# dcc_sniffer_nano.net
KiCad netlist of a schematic drawn in EAGLE
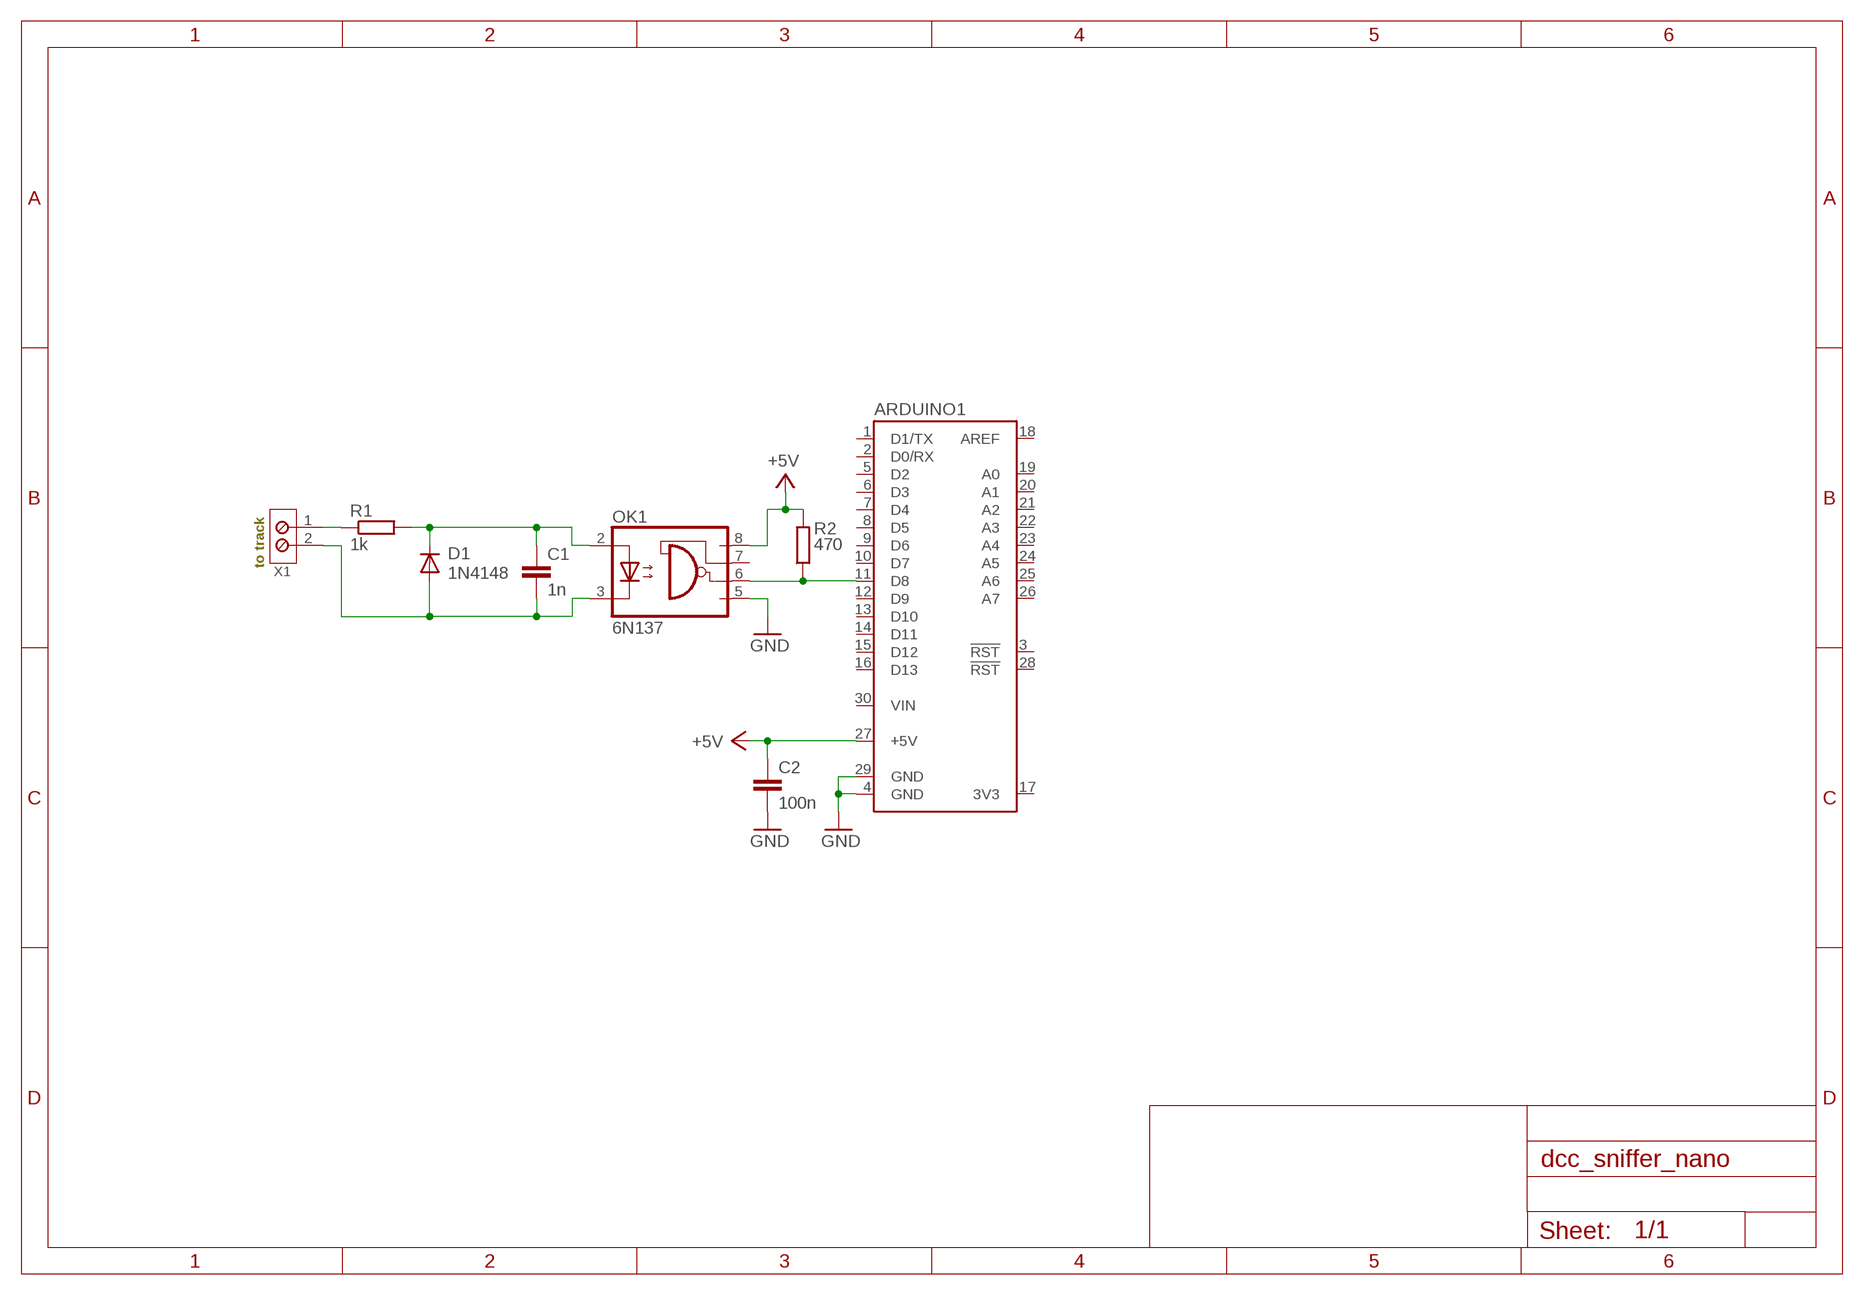
[diagram p0: schematic, sheet 1]

(export (version "E")
  (design (tool "Eeschema 10.0.6"))
  (components
    (comp (ref "ARDUINO1")
      (value "ARDUINO_NANO")
      (footprint "eagle-import:ARDUINO_NANO")
      (libsource (lib "eagle-import") (part "ARDUINO_NANO"))
    )
    (comp (ref "C1")
      (value "1n")
      (footprint "eagle-import:C025-025X050")
      (libsource (lib "eagle-import") (part "C-EU025-025X050"))
    )
    (comp (ref "C2")
      (value "100n")
      (footprint "eagle-import:C025-025X050")
      (libsource (lib "eagle-import") (part "C-EU025-025X050"))
    )
    (comp (ref "D1")
      (value "1N4148")
      (footprint "eagle-import:DO35_L10M0")
      (libsource (lib "eagle-import") (part "1N4148"))
    )
    (comp (ref "OK1")
      (value "6N137")
      (footprint "eagle-import:DIL08")
      (libsource (lib "eagle-import") (part "6N137"))
    )
    (comp (ref "R1")
      (value "1k")
      (footprint "eagle-import:0207_10")
      (libsource (lib "eagle-import") (part "R-EU_0207/10"))
    )
    (comp (ref "R2")
      (value "470")
      (footprint "eagle-import:0207_10")
      (libsource (lib "eagle-import") (part "R-EU_0207/10"))
    )
    (comp (ref "X1")
      (value "RT034 Typ 086")
      (footprint "eagle-import:RT03402T086")
      (libsource (lib "eagle-import") (part "SCWTRMX02-3M81"))
    )
  )
  (nets
    (net (code "1") (name "+5V") (class "Default")
      (node (ref "ARDUINO1") (pin "27") (pinfunction "+5V_27") (pintype "power_in"))
      (node (ref "C2") (pin "1") (pinfunction "1_1") (pintype "passive"))
      (node (ref "OK1") (pin "8") (pinfunction "VCC_8") (pintype "passive"))
      (node (ref "R2") (pin "2") (pinfunction "2_2") (pintype "passive"))
    )
    (net (code "2") (name "/VIN") (class "Default")
      (node (ref "ARDUINO1") (pin "30") (pinfunction "VIN_30") (pintype "power_in"))
    )
    (net (code "3") (name "GND") (class "Default")
      (node (ref "ARDUINO1") (pin "29") (pinfunction "GND_29") (pintype "power_in"))
      (node (ref "ARDUINO1") (pin "4") (pinfunction "GND_4") (pintype "power_in"))
      (node (ref "C2") (pin "2") (pinfunction "2_2") (pintype "passive"))
      (node (ref "OK1") (pin "5") (pinfunction "GND_5") (pintype "passive"))
    )
    (net (code "4") (name "Net-(ARDUINO1-D8)") (class "Default")
      (node (ref "ARDUINO1") (pin "11") (pinfunction "D8_11") (pintype "bidirectional"))
      (node (ref "OK1") (pin "6") (pinfunction "VO_6") (pintype "passive"))
      (node (ref "R2") (pin "1") (pinfunction "1_1") (pintype "passive"))
    )
    (net (code "5") (name "Net-(OK1-A)") (class "Default")
      (node (ref "C1") (pin "1") (pinfunction "1_1") (pintype "passive"))
      (node (ref "D1") (pin "C") (pinfunction "C_C") (pintype "passive"))
      (node (ref "OK1") (pin "2") (pinfunction "A_2") (pintype "passive"))
      (node (ref "R1") (pin "2") (pinfunction "2_2") (pintype "passive"))
    )
    (net (code "6") (name "Net-(OK1-C)") (class "Default")
      (node (ref "C1") (pin "2") (pinfunction "2_2") (pintype "passive"))
      (node (ref "D1") (pin "A") (pinfunction "A_A") (pintype "passive"))
      (node (ref "OK1") (pin "3") (pinfunction "C_3") (pintype "passive"))
      (node (ref "X1") (pin "2") (pinfunction "P$1_2") (pintype "bidirectional"))
    )
    (net (code "7") (name "Net-(X1A-P$1)") (class "Default")
      (node (ref "R1") (pin "1") (pinfunction "1_1") (pintype "passive"))
      (node (ref "X1") (pin "1") (pinfunction "P$1_1") (pintype "bidirectional"))
    )
    (net (code "8") (name "unconnected-(ARDUINO1-3V3-Pad17)") (class "Default")
      (node (ref "ARDUINO1") (pin "17") (pinfunction "3V3_17") (pintype "output"))
    )
    (net (code "9") (name "unconnected-(ARDUINO1-A0-Pad19)") (class "Default")
      (node (ref "ARDUINO1") (pin "19") (pinfunction "A0_19") (pintype "input"))
    )
    (net (code "10") (name "unconnected-(ARDUINO1-A1-Pad20)") (class "Default")
      (node (ref "ARDUINO1") (pin "20") (pinfunction "A1_20") (pintype "input"))
    )
    (net (code "11") (name "unconnected-(ARDUINO1-A2-Pad21)") (class "Default")
      (node (ref "ARDUINO1") (pin "21") (pinfunction "A2_21") (pintype "input"))
    )
    (net (code "12") (name "unconnected-(ARDUINO1-A3-Pad22)") (class "Default")
      (node (ref "ARDUINO1") (pin "22") (pinfunction "A3_22") (pintype "input"))
    )
    (net (code "13") (name "unconnected-(ARDUINO1-A4-Pad23)") (class "Default")
      (node (ref "ARDUINO1") (pin "23") (pinfunction "A4_23") (pintype "input"))
    )
    (net (code "14") (name "unconnected-(ARDUINO1-A5-Pad24)") (class "Default")
      (node (ref "ARDUINO1") (pin "24") (pinfunction "A5_24") (pintype "input"))
    )
    (net (code "15") (name "unconnected-(ARDUINO1-A6-Pad25)") (class "Default")
      (node (ref "ARDUINO1") (pin "25") (pinfunction "A6_25") (pintype "input"))
    )
    (net (code "16") (name "unconnected-(ARDUINO1-A7-Pad26)") (class "Default")
      (node (ref "ARDUINO1") (pin "26") (pinfunction "A7_26") (pintype "input"))
    )
    (net (code "17") (name "unconnected-(ARDUINO1-AREF-Pad18)") (class "Default")
      (node (ref "ARDUINO1") (pin "18") (pinfunction "AREF_18") (pintype "input"))
    )
    (net (code "18") (name "unconnected-(ARDUINO1-D0{slash}RX-Pad2)") (class "Default")
      (node (ref "ARDUINO1") (pin "2") (pinfunction "D0/RX_2") (pintype "bidirectional"))
    )
    (net (code "19") (name "unconnected-(ARDUINO1-D1{slash}TX-Pad1)") (class "Default")
      (node (ref "ARDUINO1") (pin "1") (pinfunction "D1/TX_1") (pintype "bidirectional"))
    )
    (net (code "20") (name "unconnected-(ARDUINO1-D2-Pad5)") (class "Default")
      (node (ref "ARDUINO1") (pin "5") (pinfunction "D2_5") (pintype "bidirectional"))
    )
    (net (code "21") (name "unconnected-(ARDUINO1-D3-Pad6)") (class "Default")
      (node (ref "ARDUINO1") (pin "6") (pinfunction "D3_6") (pintype "bidirectional"))
    )
    (net (code "22") (name "unconnected-(ARDUINO1-D4-Pad7)") (class "Default")
      (node (ref "ARDUINO1") (pin "7") (pinfunction "D4_7") (pintype "bidirectional"))
    )
    (net (code "23") (name "unconnected-(ARDUINO1-D5-Pad8)") (class "Default")
      (node (ref "ARDUINO1") (pin "8") (pinfunction "D5_8") (pintype "bidirectional"))
    )
    (net (code "24") (name "unconnected-(ARDUINO1-D6-Pad9)") (class "Default")
      (node (ref "ARDUINO1") (pin "9") (pinfunction "D6_9") (pintype "bidirectional"))
    )
    (net (code "25") (name "unconnected-(ARDUINO1-D7-Pad10)") (class "Default")
      (node (ref "ARDUINO1") (pin "10") (pinfunction "D7_10") (pintype "bidirectional"))
    )
    (net (code "26") (name "unconnected-(ARDUINO1-D9-Pad12)") (class "Default")
      (node (ref "ARDUINO1") (pin "12") (pinfunction "D9_12") (pintype "bidirectional"))
    )
    (net (code "27") (name "unconnected-(ARDUINO1-D10-Pad13)") (class "Default")
      (node (ref "ARDUINO1") (pin "13") (pinfunction "D10_13") (pintype "bidirectional"))
    )
    (net (code "28") (name "unconnected-(ARDUINO1-D11-Pad14)") (class "Default")
      (node (ref "ARDUINO1") (pin "14") (pinfunction "D11_14") (pintype "bidirectional"))
    )
    (net (code "29") (name "unconnected-(ARDUINO1-D12-Pad15)") (class "Default")
      (node (ref "ARDUINO1") (pin "15") (pinfunction "D12_15") (pintype "bidirectional"))
    )
    (net (code "30") (name "unconnected-(ARDUINO1-D13-Pad16)") (class "Default")
      (node (ref "ARDUINO1") (pin "16") (pinfunction "D13_16") (pintype "bidirectional"))
    )
    (net (code "31") (name "unconnected-(ARDUINO1-~{RST}-Pad3)") (class "Default")
      (node (ref "ARDUINO1") (pin "3") (pinfunction "~{RST}_3") (pintype "input"))
    )
    (net (code "32") (name "unconnected-(ARDUINO1-~{RST}-Pad28)") (class "Default")
      (node (ref "ARDUINO1") (pin "28") (pinfunction "~{RST}_28") (pintype "input"))
    )
    (net (code "33") (name "unconnected-(OK1-VE-Pad7)") (class "Default")
      (node (ref "OK1") (pin "7") (pinfunction "VE_7") (pintype "passive"))
    )
  )
)
